# PCB_Telemetria_2020.net
KiCad netlist of a schematic drawn in EAGLE
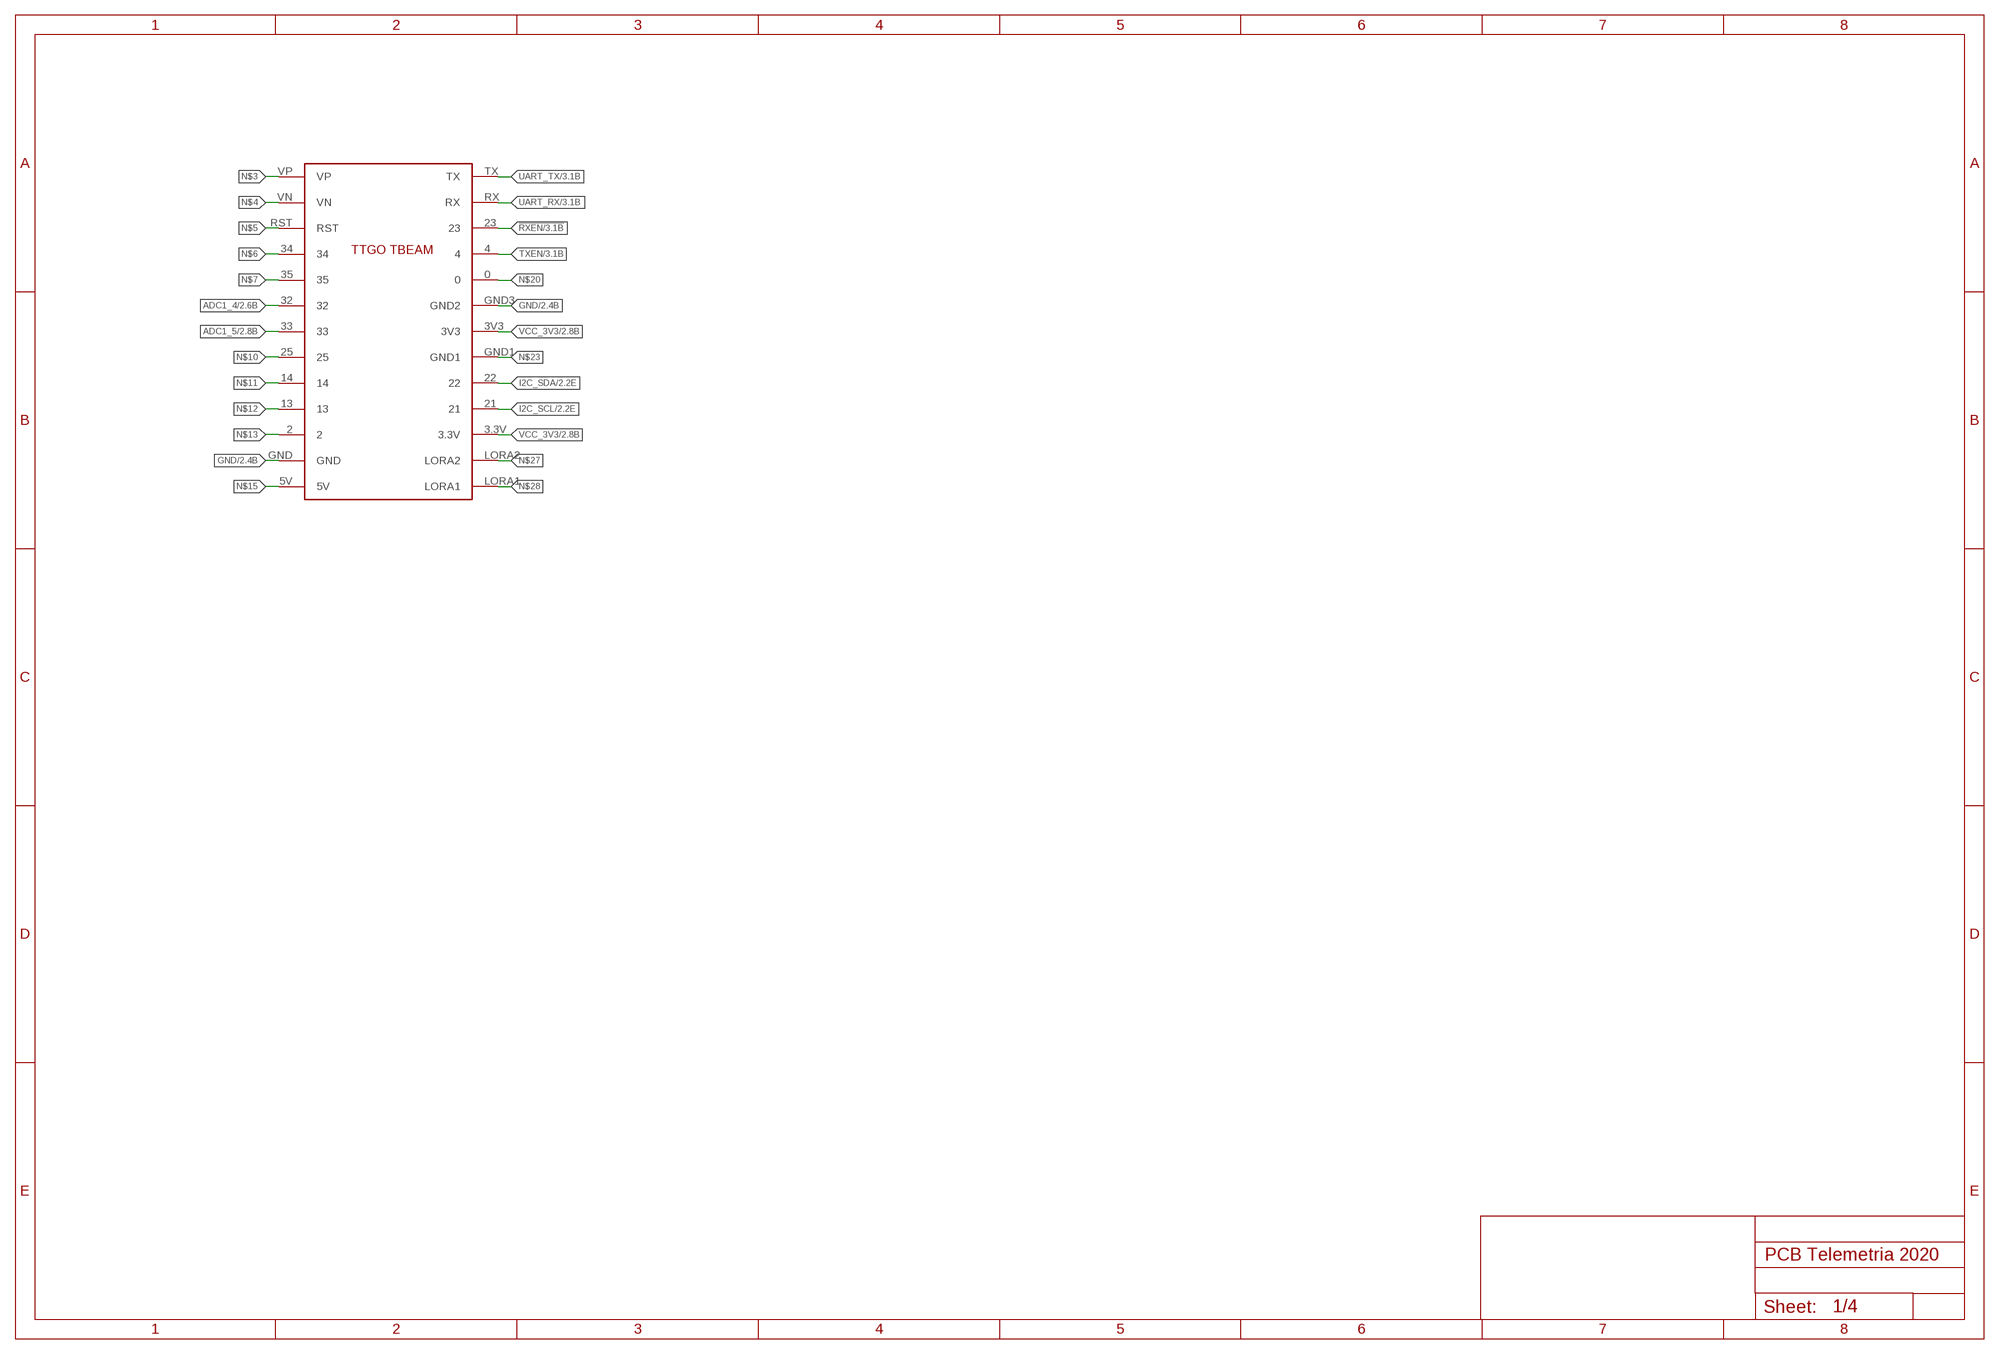
[diagram p0: schematic, sheet 1]
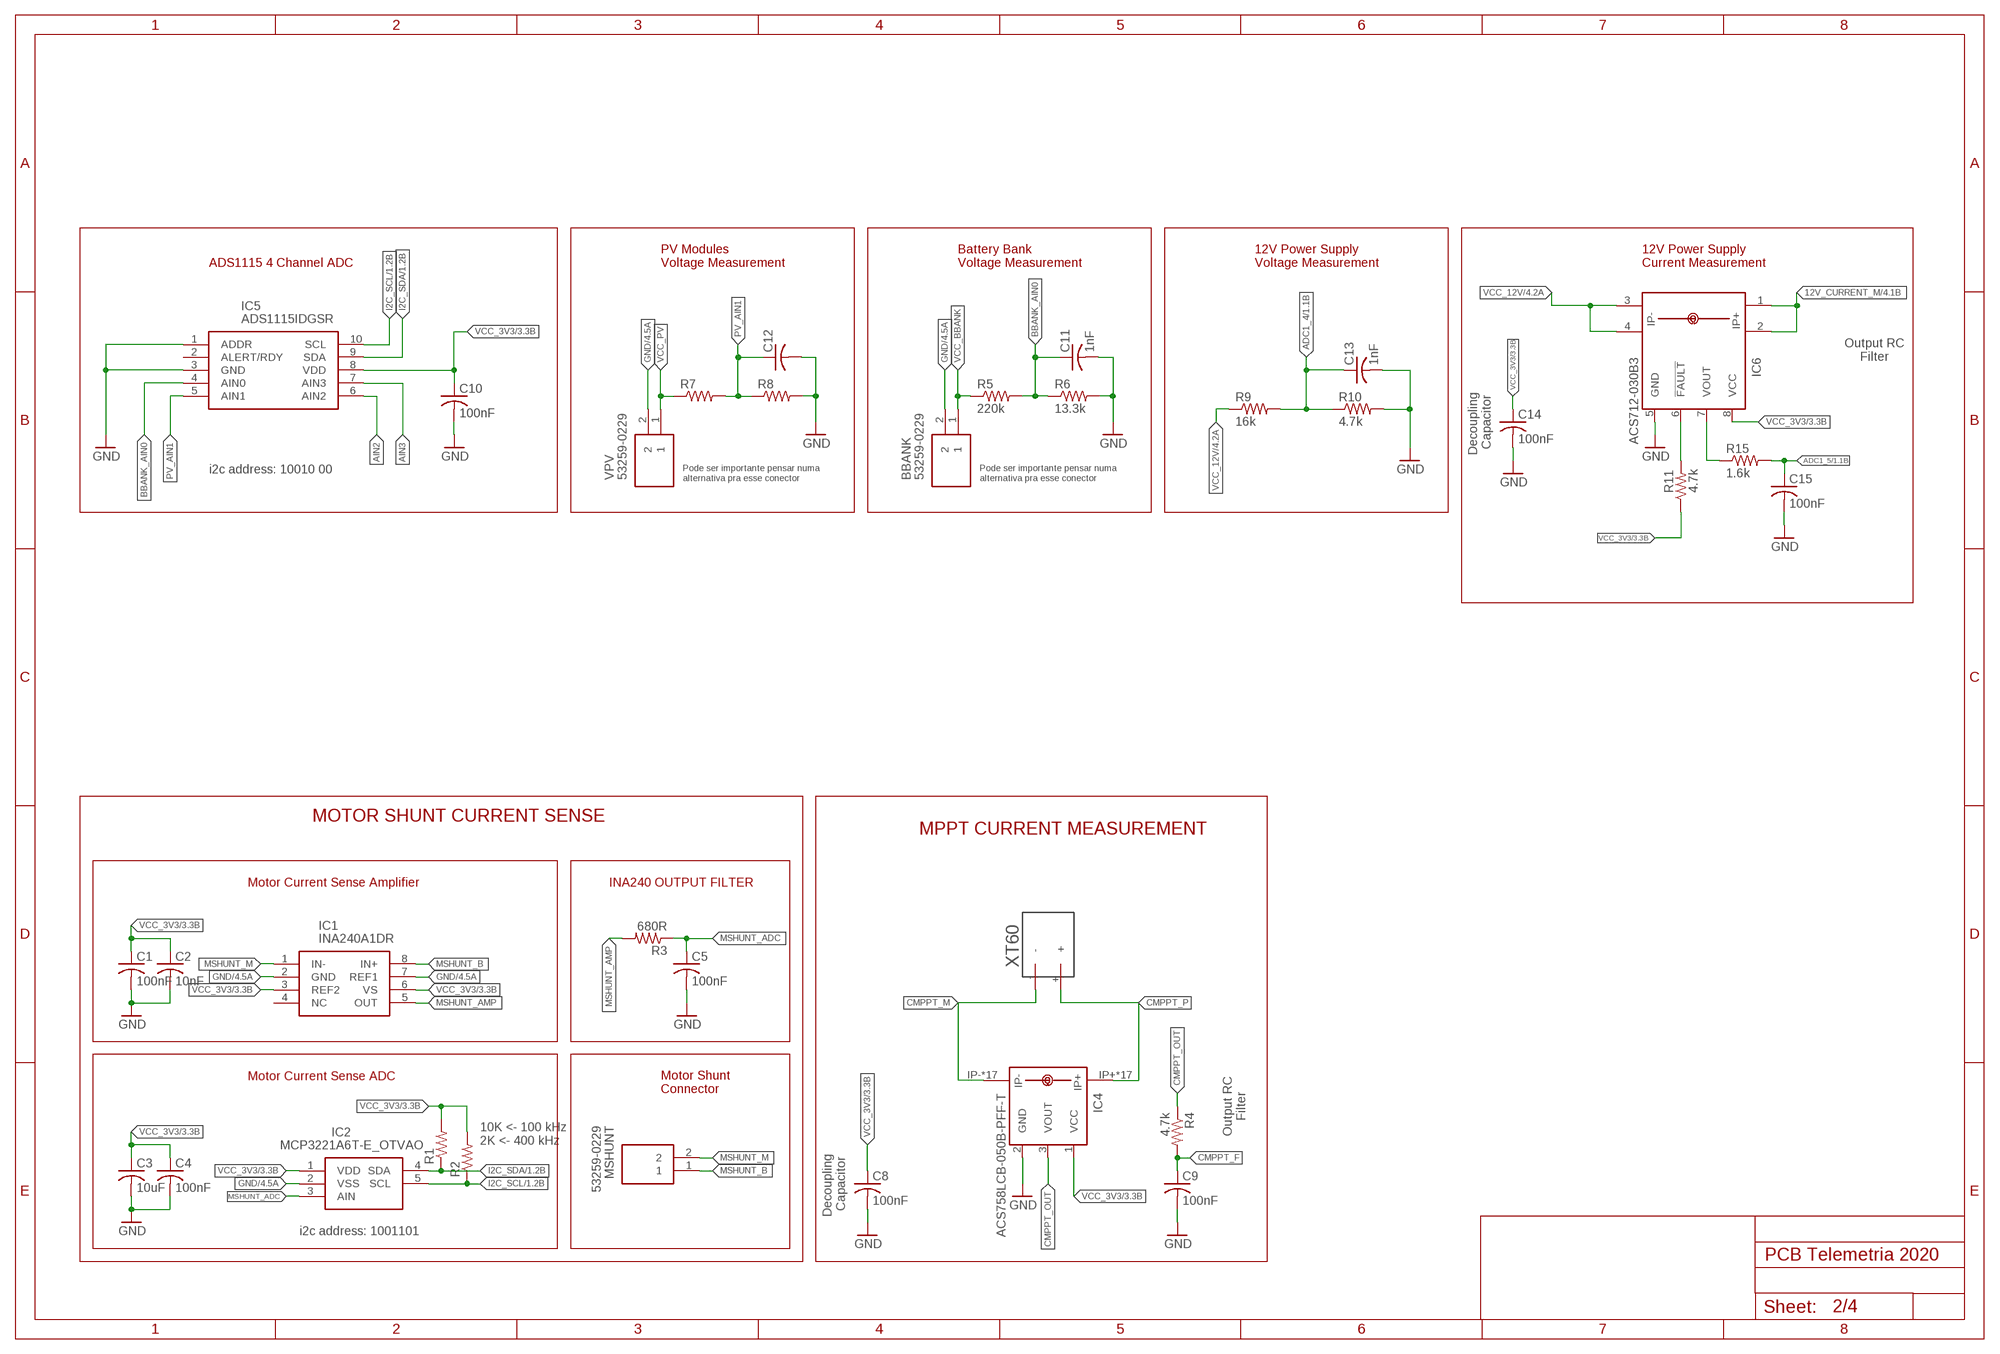
[diagram p1: schematic, sheet 2]
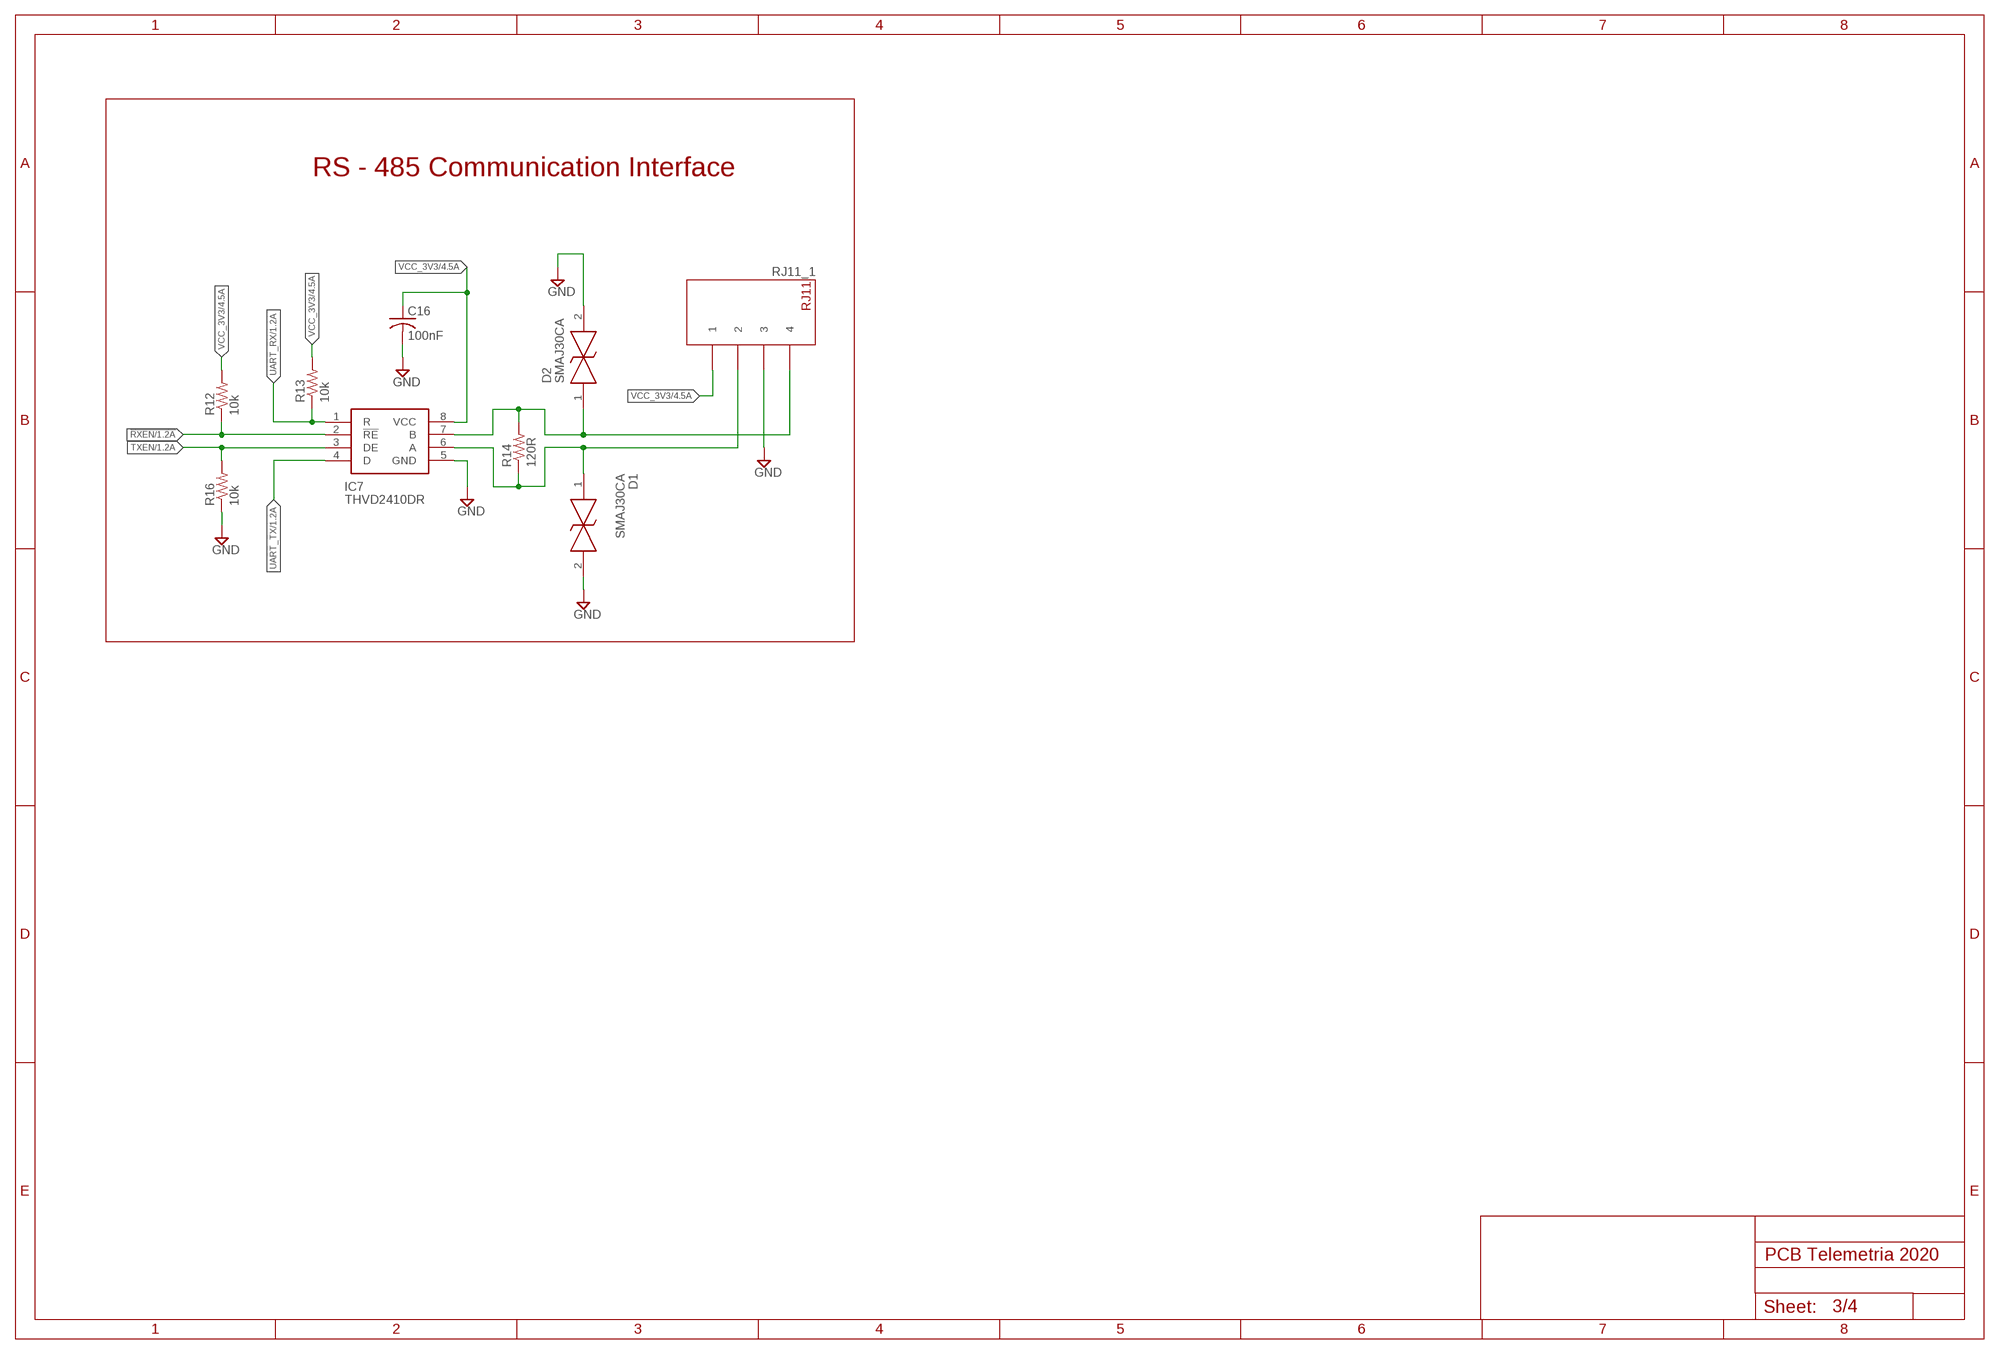
[diagram p2: schematic, sheet 3]
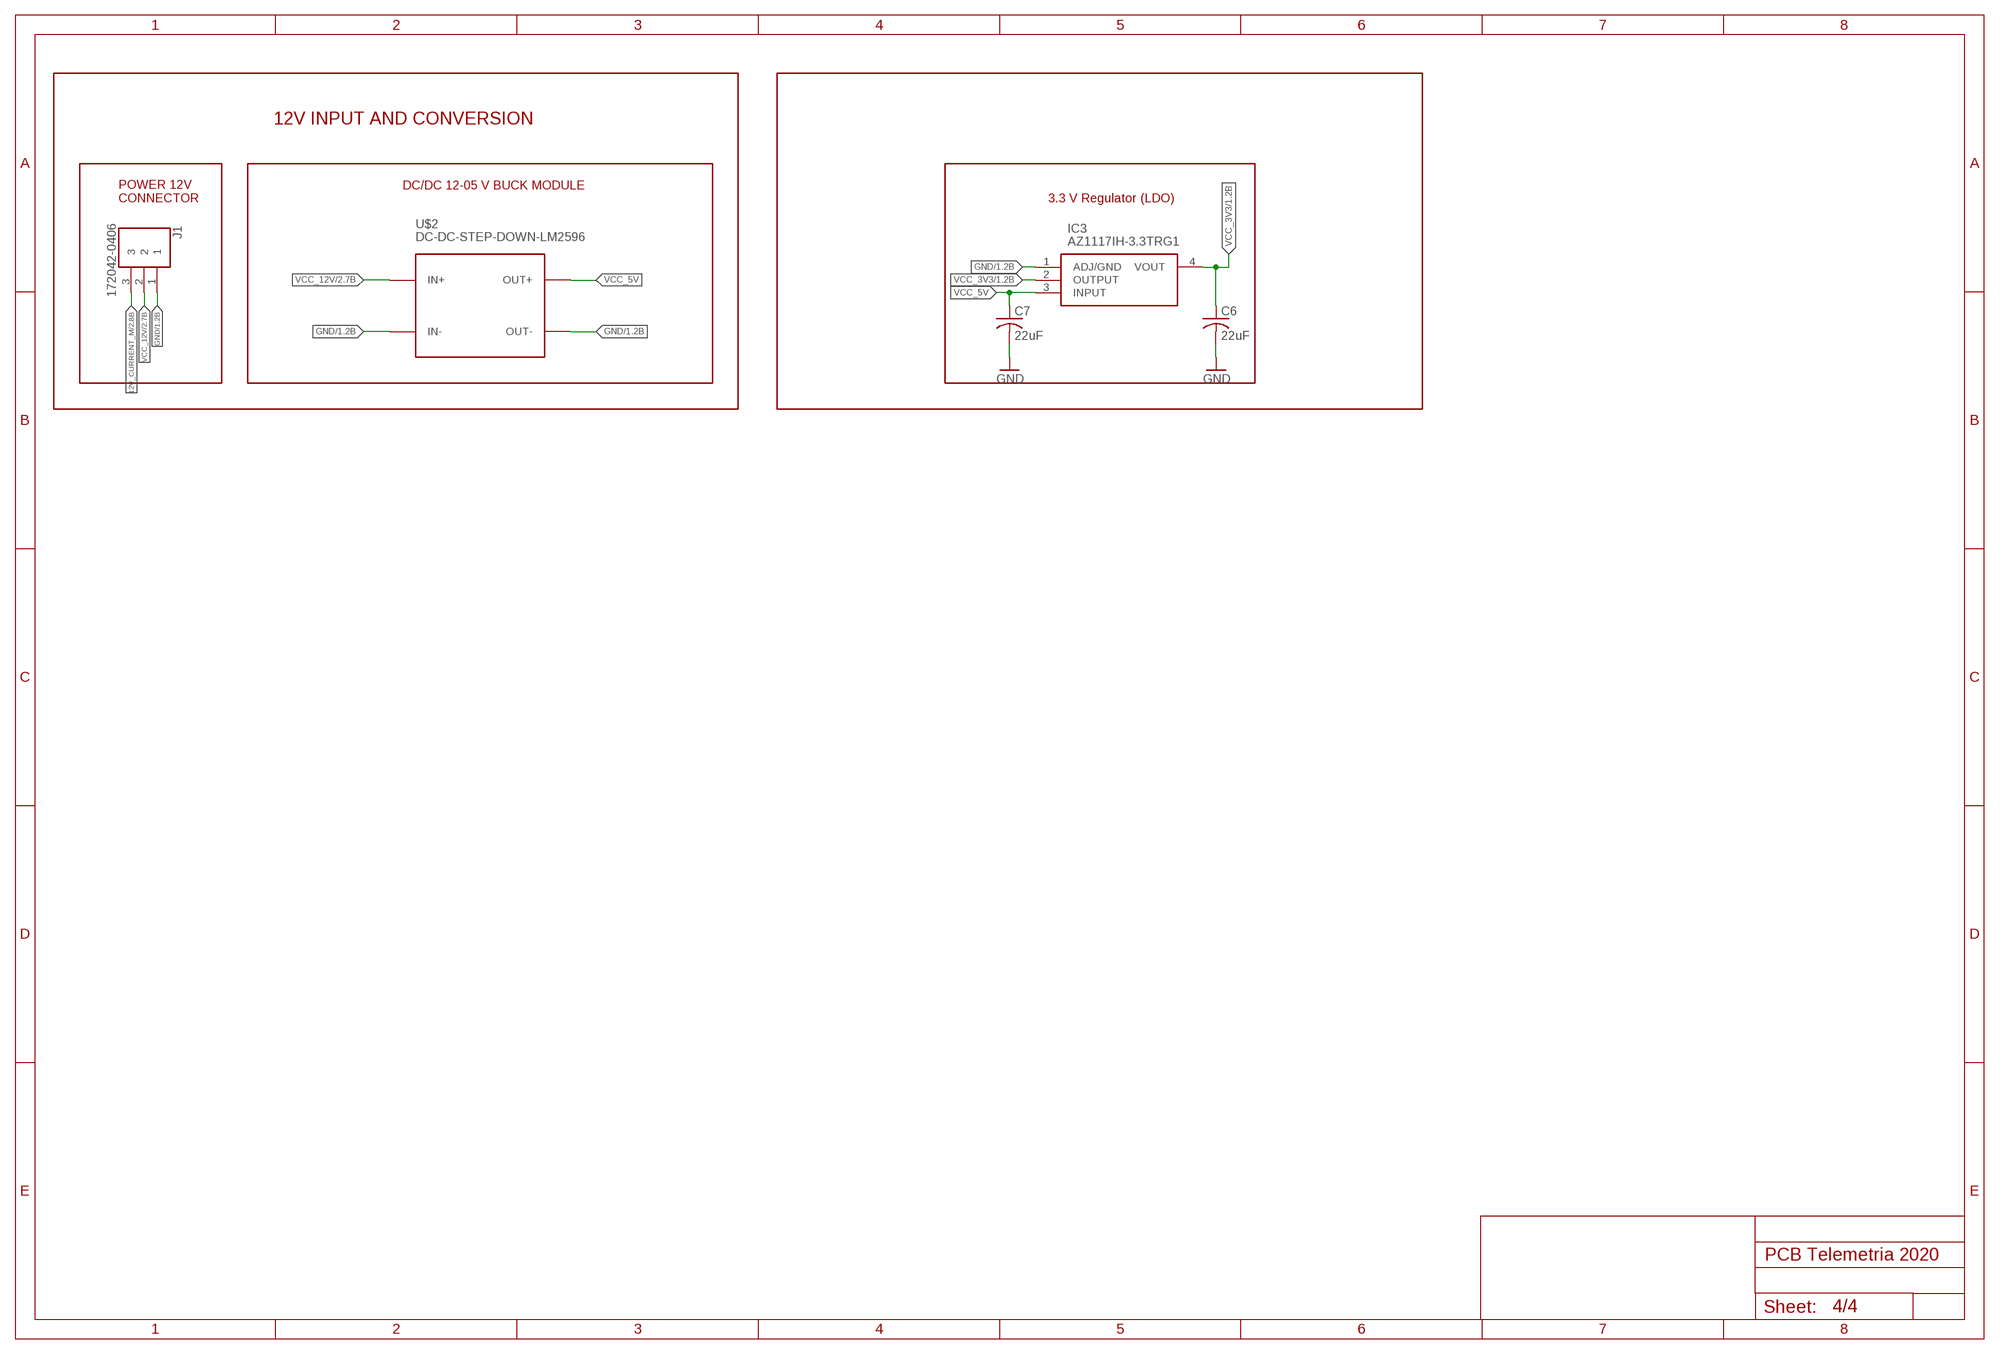
[diagram p3: schematic, sheet 4]

(export (version "E")
  (design (tool "Eeschema 10.0.6"))
  (components
    (comp (ref "U$1")
      (value "TTGOBEAM")
      (footprint "eagle-import:TTGOBEAM")
      (libsource (lib "eagle-import") (part "TTGOBEAM"))
    )
    (comp (ref "BBANK")
      (value "53259-0229")
      (footprint "eagle-import:0532590229")
      (fields (field (name "MOUSER_PART_NUMBER") "538-53259-0229"))
      (libsource (lib "eagle-import") (part "53259-0229"))
    )
    (comp (ref "C1")
      (value "100nF")
      (footprint "eagle-import:C0805")
      (libsource (lib "eagle-import") (part "C-USC0805"))
    )
    (comp (ref "C2")
      (value "10nF")
      (footprint "eagle-import:C0805")
      (libsource (lib "eagle-import") (part "C-USC0805"))
    )
    (comp (ref "C3")
      (value "10uF")
      (footprint "eagle-import:C0805")
      (libsource (lib "eagle-import") (part "C-USC0805"))
    )
    (comp (ref "C4")
      (value "100nF")
      (footprint "eagle-import:C0805")
      (libsource (lib "eagle-import") (part "C-USC0805"))
    )
    (comp (ref "C5")
      (value "100nF")
      (footprint "eagle-import:C0805")
      (libsource (lib "eagle-import") (part "C-USC0805"))
    )
    (comp (ref "C8")
      (value "100nF")
      (footprint "eagle-import:C0805")
      (libsource (lib "eagle-import") (part "C-USC0805"))
    )
    (comp (ref "C9")
      (value "100nF")
      (footprint "eagle-import:C0805")
      (libsource (lib "eagle-import") (part "C-USC0805"))
    )
    (comp (ref "C10")
      (value "100nF")
      (footprint "eagle-import:C0805")
      (libsource (lib "eagle-import") (part "C-USC0805"))
    )
    (comp (ref "C11")
      (value "1nF")
      (footprint "eagle-import:C0805")
      (libsource (lib "eagle-import") (part "C-USC0805"))
    )
    (comp (ref "C12")
      (value "C-USC0805")
      (footprint "eagle-import:C0805")
      (libsource (lib "eagle-import") (part "C-USC0805"))
    )
    (comp (ref "C13")
      (value "1nF")
      (footprint "eagle-import:C0805")
      (libsource (lib "eagle-import") (part "C-USC0805"))
    )
    (comp (ref "C14")
      (value "100nF")
      (footprint "eagle-import:C0805")
      (libsource (lib "eagle-import") (part "C-USC0805"))
    )
    (comp (ref "C15")
      (value "100nF")
      (footprint "eagle-import:C0805")
      (libsource (lib "eagle-import") (part "C-USC0805"))
    )
    (comp (ref "IC1")
      (value "INA240A1DR")
      (footprint "eagle-import:SOIC127P600X175-8N")
      (fields (field (name "MOUSER_PART_NUMBER") "595-INA240A1DR"))
      (libsource (lib "eagle-import") (part "INA240A1DR"))
    )
    (comp (ref "IC2")
      (value "MCP3221A6T-E_OTVAO")
      (footprint "eagle-import:SOT95P280X145-5N")
      (fields
        (field (name "MANUFACTURER_PART_NUMBER") "MCP3221A6T-E/OTVAO")
        (field (name "MOUSER_PART_NUMBER") "579-MCP3221A6TEOTVAO")
      )
      (libsource (lib "eagle-import") (part "MCP3221A6T-E_OTVAO"))
    )
    (comp (ref "IC4")
      (value "ACS758LCB-050B-PFF-T")
      (footprint "eagle-import:CB-PFF")
      (libsource (lib "eagle-import") (part "ACS758LCB-050B-PFF-T"))
    )
    (comp (ref "IC5")
      (value "ADS1115IDGSR")
      (footprint "eagle-import:SOP50P490X110-10N")
      (fields (field (name "MOUSER_PART_NUMBER") "595-ADS1115IDGSR"))
      (libsource (lib "eagle-import") (part "ADS1115IDGSR"))
    )
    (comp (ref "IC6")
      (value "ACS712-030B3")
      (footprint "eagle-import:SOIC8")
      (libsource (lib "eagle-import") (part "ACS712-LC"))
    )
    (comp (ref "MSHUNT")
      (value "53259-0229")
      (footprint "eagle-import:0532590229")
      (fields (field (name "MOUSER_PART_NUMBER") "538-53259-0229"))
      (libsource (lib "eagle-import") (part "53259-0229"))
    )
    (comp (ref "R1")
      (value "R-US_R0805")
      (footprint "eagle-import:R0805")
      (libsource (lib "eagle-import") (part "R-US_R0805"))
    )
    (comp (ref "R2")
      (value "R-US_R0805")
      (footprint "eagle-import:R0805")
      (libsource (lib "eagle-import") (part "R-US_R0805"))
    )
    (comp (ref "R3")
      (value "680R")
      (footprint "eagle-import:R0805")
      (libsource (lib "eagle-import") (part "R-US_R0805"))
    )
    (comp (ref "R4")
      (value "4.7k")
      (footprint "eagle-import:R0805")
      (libsource (lib "eagle-import") (part "R-US_R0805"))
    )
    (comp (ref "R5")
      (value "220k")
      (footprint "eagle-import:R0805")
      (libsource (lib "eagle-import") (part "R-US_R0805"))
    )
    (comp (ref "R6")
      (value "13.3k")
      (footprint "eagle-import:R0805")
      (libsource (lib "eagle-import") (part "R-US_R0805"))
    )
    (comp (ref "R7")
      (value "R-US_R0805")
      (footprint "eagle-import:R0805")
      (libsource (lib "eagle-import") (part "R-US_R0805"))
    )
    (comp (ref "R8")
      (value "R-US_R0805")
      (footprint "eagle-import:R0805")
      (libsource (lib "eagle-import") (part "R-US_R0805"))
    )
    (comp (ref "R9")
      (value "16k")
      (footprint "eagle-import:R0805")
      (libsource (lib "eagle-import") (part "R-US_R0805"))
    )
    (comp (ref "R10")
      (value "4.7k")
      (footprint "eagle-import:R0805")
      (libsource (lib "eagle-import") (part "R-US_R0805"))
    )
    (comp (ref "R11")
      (value "4.7k")
      (footprint "eagle-import:R0805")
      (libsource (lib "eagle-import") (part "R-US_R0805"))
    )
    (comp (ref "R15")
      (value "1.6k")
      (footprint "eagle-import:R0805")
      (libsource (lib "eagle-import") (part "R-US_R0805"))
    )
    (comp (ref "U$3")
      (value "XT60")
      (footprint "eagle-import:XT60")
      (libsource (lib "eagle-import") (part "XT60"))
    )
    (comp (ref "VPV")
      (value "53259-0229")
      (footprint "eagle-import:0532590229")
      (fields (field (name "MOUSER_PART_NUMBER") "538-53259-0229"))
      (libsource (lib "eagle-import") (part "53259-0229"))
    )
    (comp (ref "C16")
      (value "100nF")
      (footprint "eagle-import:C0805")
      (libsource (lib "eagle-import") (part "C-USC0805"))
    )
    (comp (ref "D1")
      (value "SMAJ30CA")
      (footprint "eagle-import:DIONM5026X229N")
      (fields (field (name "MOUSER_PART_NUMBER") "576-SMAJ30CA"))
      (libsource (lib "eagle-import") (part "SMAJ30CA"))
    )
    (comp (ref "D2")
      (value "SMAJ30CA")
      (footprint "eagle-import:DIONM5026X229N")
      (fields (field (name "MOUSER_PART_NUMBER") "576-SMAJ30CA"))
      (libsource (lib "eagle-import") (part "SMAJ30CA"))
    )
    (comp (ref "IC7")
      (value "THVD2410DR")
      (footprint "eagle-import:SOIC127P600X175-8N")
      (fields (field (name "MOUSER_PART_NUMBER") "595-THVD2410DR"))
      (libsource (lib "eagle-import") (part "THVD2410DR"))
    )
    (comp (ref "R12")
      (value "10k")
      (footprint "eagle-import:M0805")
      (libsource (lib "eagle-import") (part "R-US_M0805"))
    )
    (comp (ref "R13")
      (value "10k")
      (footprint "eagle-import:M0805")
      (libsource (lib "eagle-import") (part "R-US_M0805"))
    )
    (comp (ref "R14")
      (value "120R")
      (footprint "eagle-import:M0805")
      (libsource (lib "eagle-import") (part "R-US_M0805"))
    )
    (comp (ref "R16")
      (value "10k")
      (footprint "eagle-import:M0805")
      (libsource (lib "eagle-import") (part "R-US_M0805"))
    )
    (comp (ref "RJ11_1")
      (value "TFC44")
      (footprint "eagle-import:TFC44")
      (libsource (lib "eagle-import") (part "TFC44"))
    )
    (comp (ref "C6")
      (value "22uF")
      (footprint "eagle-import:C0805")
      (libsource (lib "eagle-import") (part "C-USC0805"))
    )
    (comp (ref "C7")
      (value "22uF")
      (footprint "eagle-import:C0805")
      (libsource (lib "eagle-import") (part "C-USC0805"))
    )
    (comp (ref "IC3")
      (value "AZ1117IH-3.3TRG1")
      (footprint "eagle-import:SOT230P700X170-4N")
      (fields (field (name "MOUSER_PART_NUMBER") "621-AZ1117IH-3.3TRG1"))
      (libsource (lib "eagle-import") (part "AZ1117IH-3.3TRG1"))
    )
    (comp (ref "J1")
      (value "172042-0406")
      (footprint "eagle-import:MOLEX_172042-0406")
      (fields (field (name "MF") "Molex") (field (name "MP") "172042-0302"))
      (libsource (lib "eagle-import") (part "172042-0406"))
    )
    (comp (ref "U$2")
      (value "DC-DC-STEP-DOWN-LM2596")
      (footprint "eagle-import:DC-DC-STEP-DOWN-LM2596")
      (libsource (lib "eagle-import") (part "DC-DC-STEP-DOWN-LM2596"))
    )
  )
  (nets
    (net (code "1") (name "12V_CURRENT_M") (class "Default")
      (node (ref "IC6") (pin "1") (pinfunction "IP+_1") (pintype "passive"))
      (node (ref "IC6") (pin "2") (pinfunction "IP+1_2") (pintype "passive"))
      (node (ref "J1") (pin "3") (pinfunction "3_3") (pintype "passive"))
    )
    (net (code "2") (name "ADC1_4") (class "Default")
      (node (ref "C13") (pin "1") (pinfunction "1_1") (pintype "passive"))
      (node (ref "R10") (pin "1") (pinfunction "1_1") (pintype "passive"))
      (node (ref "R9") (pin "2") (pinfunction "2_2") (pintype "passive"))
      (node (ref "U$1") (pin "32") (pinfunction "32_32") (pintype "bidirectional"))
    )
    (net (code "3") (name "ADC1_5") (class "Default")
      (node (ref "C15") (pin "1") (pinfunction "1_1") (pintype "passive"))
      (node (ref "R15") (pin "2") (pinfunction "2_2") (pintype "passive"))
      (node (ref "U$1") (pin "33") (pinfunction "33_33") (pintype "bidirectional"))
    )
    (net (code "4") (name "AIN2") (class "Default")
      (node (ref "IC5") (pin "6") (pinfunction "AIN2_6") (pintype "bidirectional"))
    )
    (net (code "5") (name "AIN3") (class "Default")
      (node (ref "IC5") (pin "7") (pinfunction "AIN3_7") (pintype "bidirectional"))
    )
    (net (code "6") (name "BBANK_AIN0") (class "Default")
      (node (ref "C11") (pin "1") (pinfunction "1_1") (pintype "passive"))
      (node (ref "IC5") (pin "4") (pinfunction "AIN0_4") (pintype "bidirectional"))
      (node (ref "R5") (pin "2") (pinfunction "2_2") (pintype "passive"))
      (node (ref "R6") (pin "1") (pinfunction "1_1") (pintype "passive"))
    )
    (net (code "7") (name "CMPPT_F") (class "Default")
      (node (ref "C9") (pin "1") (pinfunction "1_1") (pintype "passive"))
      (node (ref "R4") (pin "2") (pinfunction "2_2") (pintype "passive"))
    )
    (net (code "8") (name "CMPPT_M") (class "Default")
      (node (ref "IC4") (pin "IP-") (pinfunction "IP-_IP-") (pintype "passive"))
      (node (ref "IC4") (pin "IP-@10") (pinfunction "IP-_IP-@10") (pintype "passive"))
      (node (ref "IC4") (pin "IP-@11") (pinfunction "IP-_IP-@11") (pintype "passive"))
      (node (ref "IC4") (pin "IP-@12") (pinfunction "IP-_IP-@12") (pintype "passive"))
      (node (ref "IC4") (pin "IP-@13") (pinfunction "IP-_IP-@13") (pintype "passive"))
      (node (ref "IC4") (pin "IP-@14") (pinfunction "IP-_IP-@14") (pintype "passive"))
      (node (ref "IC4") (pin "IP-@15") (pinfunction "IP-_IP-@15") (pintype "passive"))
      (node (ref "IC4") (pin "IP-@16") (pinfunction "IP-_IP-@16") (pintype "passive"))
      (node (ref "IC4") (pin "IP-@17") (pinfunction "IP-_IP-@17") (pintype "passive"))
      (node (ref "IC4") (pin "IP-@2") (pinfunction "IP-_IP-@2") (pintype "passive"))
      (node (ref "IC4") (pin "IP-@3") (pinfunction "IP-_IP-@3") (pintype "passive"))
      (node (ref "IC4") (pin "IP-@4") (pinfunction "IP-_IP-@4") (pintype "passive"))
      (node (ref "IC4") (pin "IP-@5") (pinfunction "IP-_IP-@5") (pintype "passive"))
      (node (ref "IC4") (pin "IP-@6") (pinfunction "IP-_IP-@6") (pintype "passive"))
      (node (ref "IC4") (pin "IP-@7") (pinfunction "IP-_IP-@7") (pintype "passive"))
      (node (ref "IC4") (pin "IP-@8") (pinfunction "IP-_IP-@8") (pintype "passive"))
      (node (ref "IC4") (pin "IP-@9") (pinfunction "IP-_IP-@9") (pintype "passive"))
      (node (ref "U$3") (pin "-") (pinfunction "-_-") (pintype "bidirectional"))
    )
    (net (code "9") (name "CMPPT_OUT") (class "Default")
      (node (ref "IC4") (pin "3") (pinfunction "VOUT_3") (pintype "output"))
      (node (ref "R4") (pin "1") (pinfunction "1_1") (pintype "passive"))
    )
    (net (code "10") (name "CMPPT_P") (class "Default")
      (node (ref "IC4") (pin "IP+") (pinfunction "IP+_IP+") (pintype "passive"))
      (node (ref "IC4") (pin "IP+@10") (pinfunction "IP+_IP+@10") (pintype "passive"))
      (node (ref "IC4") (pin "IP+@11") (pinfunction "IP+_IP+@11") (pintype "passive"))
      (node (ref "IC4") (pin "IP+@12") (pinfunction "IP+_IP+@12") (pintype "passive"))
      (node (ref "IC4") (pin "IP+@13") (pinfunction "IP+_IP+@13") (pintype "passive"))
      (node (ref "IC4") (pin "IP+@14") (pinfunction "IP+_IP+@14") (pintype "passive"))
      (node (ref "IC4") (pin "IP+@15") (pinfunction "IP+_IP+@15") (pintype "passive"))
      (node (ref "IC4") (pin "IP+@16") (pinfunction "IP+_IP+@16") (pintype "passive"))
      (node (ref "IC4") (pin "IP+@17") (pinfunction "IP+_IP+@17") (pintype "passive"))
      (node (ref "IC4") (pin "IP+@2") (pinfunction "IP+_IP+@2") (pintype "passive"))
      (node (ref "IC4") (pin "IP+@3") (pinfunction "IP+_IP+@3") (pintype "passive"))
      (node (ref "IC4") (pin "IP+@4") (pinfunction "IP+_IP+@4") (pintype "passive"))
      (node (ref "IC4") (pin "IP+@5") (pinfunction "IP+_IP+@5") (pintype "passive"))
      (node (ref "IC4") (pin "IP+@6") (pinfunction "IP+_IP+@6") (pintype "passive"))
      (node (ref "IC4") (pin "IP+@7") (pinfunction "IP+_IP+@7") (pintype "passive"))
      (node (ref "IC4") (pin "IP+@8") (pinfunction "IP+_IP+@8") (pintype "passive"))
      (node (ref "IC4") (pin "IP+@9") (pinfunction "IP+_IP+@9") (pintype "passive"))
      (node (ref "U$3") (pin "+") (pinfunction "+_+") (pintype "bidirectional"))
    )
    (net (code "11") (name "GND") (class "Default")
      (node (ref "BBANK") (pin "2") (pinfunction "2_2") (pintype "bidirectional"))
      (node (ref "C1") (pin "2") (pinfunction "2_2") (pintype "passive"))
      (node (ref "C10") (pin "2") (pinfunction "2_2") (pintype "passive"))
      (node (ref "C11") (pin "2") (pinfunction "2_2") (pintype "passive"))
      (node (ref "C12") (pin "2") (pinfunction "2_2") (pintype "passive"))
      (node (ref "C13") (pin "2") (pinfunction "2_2") (pintype "passive"))
      (node (ref "C14") (pin "2") (pinfunction "2_2") (pintype "passive"))
      (node (ref "C15") (pin "2") (pinfunction "2_2") (pintype "passive"))
      (node (ref "C16") (pin "2") (pinfunction "2_2") (pintype "passive"))
      (node (ref "C2") (pin "2") (pinfunction "2_2") (pintype "passive"))
      (node (ref "C3") (pin "2") (pinfunction "2_2") (pintype "passive"))
      (node (ref "C4") (pin "2") (pinfunction "2_2") (pintype "passive"))
      (node (ref "C5") (pin "2") (pinfunction "2_2") (pintype "passive"))
      (node (ref "C6") (pin "2") (pinfunction "2_2") (pintype "passive"))
      (node (ref "C7") (pin "2") (pinfunction "2_2") (pintype "passive"))
      (node (ref "C8") (pin "2") (pinfunction "2_2") (pintype "passive"))
      (node (ref "C9") (pin "2") (pinfunction "2_2") (pintype "passive"))
      (node (ref "D1") (pin "2") (pinfunction "2_2") (pintype "bidirectional"))
      (node (ref "D2") (pin "2") (pinfunction "2_2") (pintype "bidirectional"))
      (node (ref "IC1") (pin "2") (pinfunction "GND_2") (pintype "bidirectional"))
      (node (ref "IC1") (pin "7") (pinfunction "REF1_7") (pintype "bidirectional"))
      (node (ref "IC2") (pin "2") (pinfunction "VSS_2") (pintype "bidirectional"))
      (node (ref "IC3") (pin "1") (pinfunction "ADJ/GND_1") (pintype "bidirectional"))
      (node (ref "IC4") (pin "2") (pinfunction "GND_2") (pintype "power_in"))
      (node (ref "IC5") (pin "1") (pinfunction "ADDR_1") (pintype "bidirectional"))
      (node (ref "IC5") (pin "3") (pinfunction "GND_3") (pintype "bidirectional"))
      (node (ref "IC6") (pin "5") (pinfunction "GND_5") (pintype "power_in"))
      (node (ref "IC7") (pin "5") (pinfunction "GND_5") (pintype "bidirectional"))
      (node (ref "J1") (pin "1") (pinfunction "1_1") (pintype "passive"))
      (node (ref "R10") (pin "2") (pinfunction "2_2") (pintype "passive"))
      (node (ref "R16") (pin "1") (pinfunction "1_1") (pintype "passive"))
      (node (ref "R6") (pin "2") (pinfunction "2_2") (pintype "passive"))
      (node (ref "R8") (pin "2") (pinfunction "2_2") (pintype "passive"))
      (node (ref "RJ11_1") (pin "P$3") (pinfunction "3_P$3") (pintype "bidirectional"))
      (node (ref "U$1") (pin "GND") (pinfunction "GND_GND") (pintype "bidirectional"))
      (node (ref "U$1") (pin "GND3") (pinfunction "GND2_GND3") (pintype "bidirectional"))
      (node (ref "U$2") (pin "IN-") (pinfunction "IN-_IN-") (pintype "bidirectional"))
      (node (ref "U$2") (pin "OUT-") (pinfunction "OUT-_OUT-") (pintype "bidirectional"))
      (node (ref "VPV") (pin "2") (pinfunction "2_2") (pintype "bidirectional"))
    )
    (net (code "12") (name "I2C_SCL") (class "Default")
      (node (ref "IC2") (pin "5") (pinfunction "SCL_5") (pintype "bidirectional"))
      (node (ref "IC5") (pin "10") (pinfunction "SCL_10") (pintype "bidirectional"))
      (node (ref "R2") (pin "1") (pinfunction "1_1") (pintype "passive"))
      (node (ref "U$1") (pin "21") (pinfunction "21_21") (pintype "bidirectional"))
    )
    (net (code "13") (name "I2C_SDA") (class "Default")
      (node (ref "IC2") (pin "4") (pinfunction "SDA_4") (pintype "bidirectional"))
      (node (ref "IC5") (pin "9") (pinfunction "SDA_9") (pintype "bidirectional"))
      (node (ref "R1") (pin "1") (pinfunction "1_1") (pintype "passive"))
      (node (ref "U$1") (pin "22") (pinfunction "22_22") (pintype "bidirectional"))
    )
    (net (code "14") (name "MSHUNT_ADC") (class "Default")
      (node (ref "C5") (pin "1") (pinfunction "1_1") (pintype "passive"))
      (node (ref "IC2") (pin "3") (pinfunction "AIN_3") (pintype "bidirectional"))
      (node (ref "R3") (pin "1") (pinfunction "1_1") (pintype "passive"))
    )
    (net (code "15") (name "MSHUNT_AMP") (class "Default")
      (node (ref "IC1") (pin "5") (pinfunction "OUT_5") (pintype "bidirectional"))
      (node (ref "R3") (pin "2") (pinfunction "2_2") (pintype "passive"))
    )
    (net (code "16") (name "MSHUNT_B") (class "Default")
      (node (ref "IC1") (pin "8") (pinfunction "IN+_8") (pintype "bidirectional"))
      (node (ref "MSHUNT") (pin "1") (pinfunction "1_1") (pintype "bidirectional"))
    )
    (net (code "17") (name "MSHUNT_M") (class "Default")
      (node (ref "IC1") (pin "1") (pinfunction "IN-_1") (pintype "bidirectional"))
      (node (ref "MSHUNT") (pin "2") (pinfunction "2_2") (pintype "bidirectional"))
    )
    (net (code "18") (name "N$3") (class "Default")
      (node (ref "U$1") (pin "VP") (pinfunction "VP_VP") (pintype "bidirectional"))
    )
    (net (code "19") (name "N$4") (class "Default")
      (node (ref "U$1") (pin "VN") (pinfunction "VN_VN") (pintype "bidirectional"))
    )
    (net (code "20") (name "N$5") (class "Default")
      (node (ref "U$1") (pin "RST") (pinfunction "RST_RST") (pintype "bidirectional"))
    )
    (net (code "21") (name "N$6") (class "Default")
      (node (ref "U$1") (pin "34") (pinfunction "34_34") (pintype "bidirectional"))
    )
    (net (code "22") (name "N$7") (class "Default")
      (node (ref "U$1") (pin "35") (pinfunction "35_35") (pintype "bidirectional"))
    )
    (net (code "23") (name "N$10") (class "Default")
      (node (ref "U$1") (pin "25") (pinfunction "25_25") (pintype "bidirectional"))
    )
    (net (code "24") (name "N$11") (class "Default")
      (node (ref "U$1") (pin "14") (pinfunction "14_14") (pintype "bidirectional"))
    )
    (net (code "25") (name "N$12") (class "Default")
      (node (ref "U$1") (pin "13") (pinfunction "13_13") (pintype "bidirectional"))
    )
    (net (code "26") (name "N$13") (class "Default")
      (node (ref "U$1") (pin "2") (pinfunction "2_2") (pintype "bidirectional"))
    )
    (net (code "27") (name "N$15") (class "Default")
      (node (ref "U$1") (pin "5V") (pinfunction "5V_5V") (pintype "bidirectional"))
    )
    (net (code "28") (name "N$20") (class "Default")
      (node (ref "U$1") (pin "0") (pinfunction "0_0") (pintype "bidirectional"))
    )
    (net (code "29") (name "N$23") (class "Default")
      (node (ref "U$1") (pin "GND1") (pinfunction "GND1_GND1") (pintype "bidirectional"))
    )
    (net (code "30") (name "N$27") (class "Default")
      (node (ref "U$1") (pin "LORA2") (pinfunction "LORA2_LORA2") (pintype "bidirectional"))
    )
    (net (code "31") (name "N$28") (class "Default")
      (node (ref "U$1") (pin "LORA1") (pinfunction "LORA1_LORA1") (pintype "bidirectional"))
    )
    (net (code "32") (name "Net-(IC6-VOUT)") (class "Default")
      (node (ref "IC6") (pin "7") (pinfunction "VOUT_7") (pintype "output"))
      (node (ref "R15") (pin "1") (pinfunction "1_1") (pintype "passive"))
    )
    (net (code "33") (name "Net-(IC6-~{FAULT})") (class "Default")
      (node (ref "IC6") (pin "6") (pinfunction "~{FAULT}_6") (pintype "bidirectional"))
      (node (ref "R11") (pin "2") (pinfunction "2_2") (pintype "passive"))
    )
    (net (code "34") (name "Net-(IC7-A)") (class "Default")
      (node (ref "D1") (pin "1") (pinfunction "1_1") (pintype "bidirectional"))
      (node (ref "IC7") (pin "6") (pinfunction "A_6") (pintype "bidirectional"))
      (node (ref "R14") (pin "1") (pinfunction "1_1") (pintype "passive"))
      (node (ref "RJ11_1") (pin "P$2") (pinfunction "2_P$2") (pintype "bidirectional"))
    )
    (net (code "35") (name "Net-(IC7-B)") (class "Default")
      (node (ref "D2") (pin "1") (pinfunction "1_1") (pintype "bidirectional"))
      (node (ref "IC7") (pin "7") (pinfunction "B_7") (pintype "bidirectional"))
      (node (ref "R14") (pin "2") (pinfunction "2_2") (pintype "passive"))
      (node (ref "RJ11_1") (pin "P$4") (pinfunction "4_P$4") (pintype "bidirectional"))
    )
    (net (code "36") (name "PV_AIN1") (class "Default")
      (node (ref "C12") (pin "1") (pinfunction "1_1") (pintype "passive"))
      (node (ref "IC5") (pin "5") (pinfunction "AIN1_5") (pintype "bidirectional"))
      (node (ref "R7") (pin "2") (pinfunction "2_2") (pintype "passive"))
      (node (ref "R8") (pin "1") (pinfunction "1_1") (pintype "passive"))
    )
    (net (code "37") (name "TXEN") (class "Default")
      (node (ref "IC7") (pin "3") (pinfunction "DE_3") (pintype "bidirectional"))
      (node (ref "R16") (pin "2") (pinfunction "2_2") (pintype "passive"))
      (node (ref "U$1") (pin "4") (pinfunction "4_4") (pintype "bidirectional"))
    )
    (net (code "38") (name "UART_RX") (class "Default")
      (node (ref "IC7") (pin "1") (pinfunction "R_1") (pintype "bidirectional"))
      (node (ref "R13") (pin "1") (pinfunction "1_1") (pintype "passive"))
      (node (ref "U$1") (pin "RX") (pinfunction "RX_RX") (pintype "bidirectional"))
    )
    (net (code "39") (name "UART_TX") (class "Default")
      (node (ref "IC7") (pin "4") (pinfunction "D_4") (pintype "bidirectional"))
      (node (ref "U$1") (pin "TX") (pinfunction "TX_TX") (pintype "bidirectional"))
    )
    (net (code "40") (name "VCC_3V3") (class "Default")
      (node (ref "C1") (pin "1") (pinfunction "1_1") (pintype "passive"))
      (node (ref "C10") (pin "1") (pinfunction "1_1") (pintype "passive"))
      (node (ref "C14") (pin "1") (pinfunction "1_1") (pintype "passive"))
      (node (ref "C16") (pin "1") (pinfunction "1_1") (pintype "passive"))
      (node (ref "C2") (pin "1") (pinfunction "1_1") (pintype "passive"))
      (node (ref "C3") (pin "1") (pinfunction "1_1") (pintype "passive"))
      (node (ref "C4") (pin "1") (pinfunction "1_1") (pintype "passive"))
      (node (ref "C6") (pin "1") (pinfunction "1_1") (pintype "passive"))
      (node (ref "C8") (pin "1") (pinfunction "1_1") (pintype "passive"))
      (node (ref "IC1") (pin "3") (pinfunction "REF2_3") (pintype "bidirectional"))
      (node (ref "IC1") (pin "6") (pinfunction "VS_6") (pintype "bidirectional"))
      (node (ref "IC2") (pin "1") (pinfunction "VDD_1") (pintype "bidirectional"))
      (node (ref "IC3") (pin "2") (pinfunction "OUTPUT_2") (pintype "bidirectional"))
      (node (ref "IC3") (pin "4") (pinfunction "VOUT_4") (pintype "bidirectional"))
      (node (ref "IC4") (pin "1") (pinfunction "VCC_1") (pintype "power_in"))
      (node (ref "IC5") (pin "8") (pinfunction "VDD_8") (pintype "bidirectional"))
      (node (ref "IC6") (pin "8") (pinfunction "VCC_8") (pintype "power_in"))
      (node (ref "IC7") (pin "8") (pinfunction "VCC_8") (pintype "bidirectional"))
      (node (ref "R1") (pin "2") (pinfunction "2_2") (pintype "passive"))
      (node (ref "R11") (pin "1") (pinfunction "1_1") (pintype "passive"))
      (node (ref "R12") (pin "2") (pinfunction "2_2") (pintype "passive"))
      (node (ref "R13") (pin "2") (pinfunction "2_2") (pintype "passive"))
      (node (ref "R2") (pin "2") (pinfunction "2_2") (pintype "passive"))
      (node (ref "RJ11_1") (pin "P$1") (pinfunction "1_P$1") (pintype "bidirectional"))
      (node (ref "U$1") (pin "3.3V") (pinfunction "3.3V_3.3V") (pintype "bidirectional"))
      (node (ref "U$1") (pin "3V3") (pinfunction "3V3_3V3") (pintype "bidirectional"))
    )
    (net (code "41") (name "VCC_5V") (class "Default")
      (node (ref "C7") (pin "1") (pinfunction "1_1") (pintype "passive"))
      (node (ref "IC3") (pin "3") (pinfunction "INPUT_3") (pintype "bidirectional"))
      (node (ref "U$2") (pin "OUT+") (pinfunction "OUT+_OUT+") (pintype "bidirectional"))
    )
    (net (code "42") (name "VCC_12V") (class "Default")
      (node (ref "IC6") (pin "3") (pinfunction "IP-_3") (pintype "passive"))
      (node (ref "IC6") (pin "4") (pinfunction "IP-1_4") (pintype "passive"))
      (node (ref "J1") (pin "2") (pinfunction "2_2") (pintype "passive"))
      (node (ref "R9") (pin "1") (pinfunction "1_1") (pintype "passive"))
      (node (ref "U$2") (pin "IN+") (pinfunction "IN+_IN+") (pintype "bidirectional"))
    )
    (net (code "43") (name "VCC_BBANK") (class "Default")
      (node (ref "BBANK") (pin "1") (pinfunction "1_1") (pintype "bidirectional"))
      (node (ref "R5") (pin "1") (pinfunction "1_1") (pintype "passive"))
    )
    (net (code "44") (name "VCC_PV") (class "Default")
      (node (ref "R7") (pin "1") (pinfunction "1_1") (pintype "passive"))
      (node (ref "VPV") (pin "1") (pinfunction "1_1") (pintype "bidirectional"))
    )
    (net (code "45") (name "unconnected-(IC1-NC-Pad4)") (class "Default")
      (node (ref "IC1") (pin "4") (pinfunction "NC_4") (pintype "no_connect"))
    )
    (net (code "46") (name "unconnected-(IC5-ALERT{slash}RDY-Pad2)") (class "Default")
      (node (ref "IC5") (pin "2") (pinfunction "ALERT/RDY_2") (pintype "bidirectional"))
    )
    (net (code "47") (name "~{RXEN}") (class "Default")
      (node (ref "IC7") (pin "2") (pinfunction "~{RE}_2") (pintype "bidirectional"))
      (node (ref "R12") (pin "1") (pinfunction "1_1") (pintype "passive"))
      (node (ref "U$1") (pin "23") (pinfunction "23_23") (pintype "bidirectional"))
    )
  )
)
